# 00_Block_Diagram.net
KiCad netlist of a schematic drawn in Altium Designer
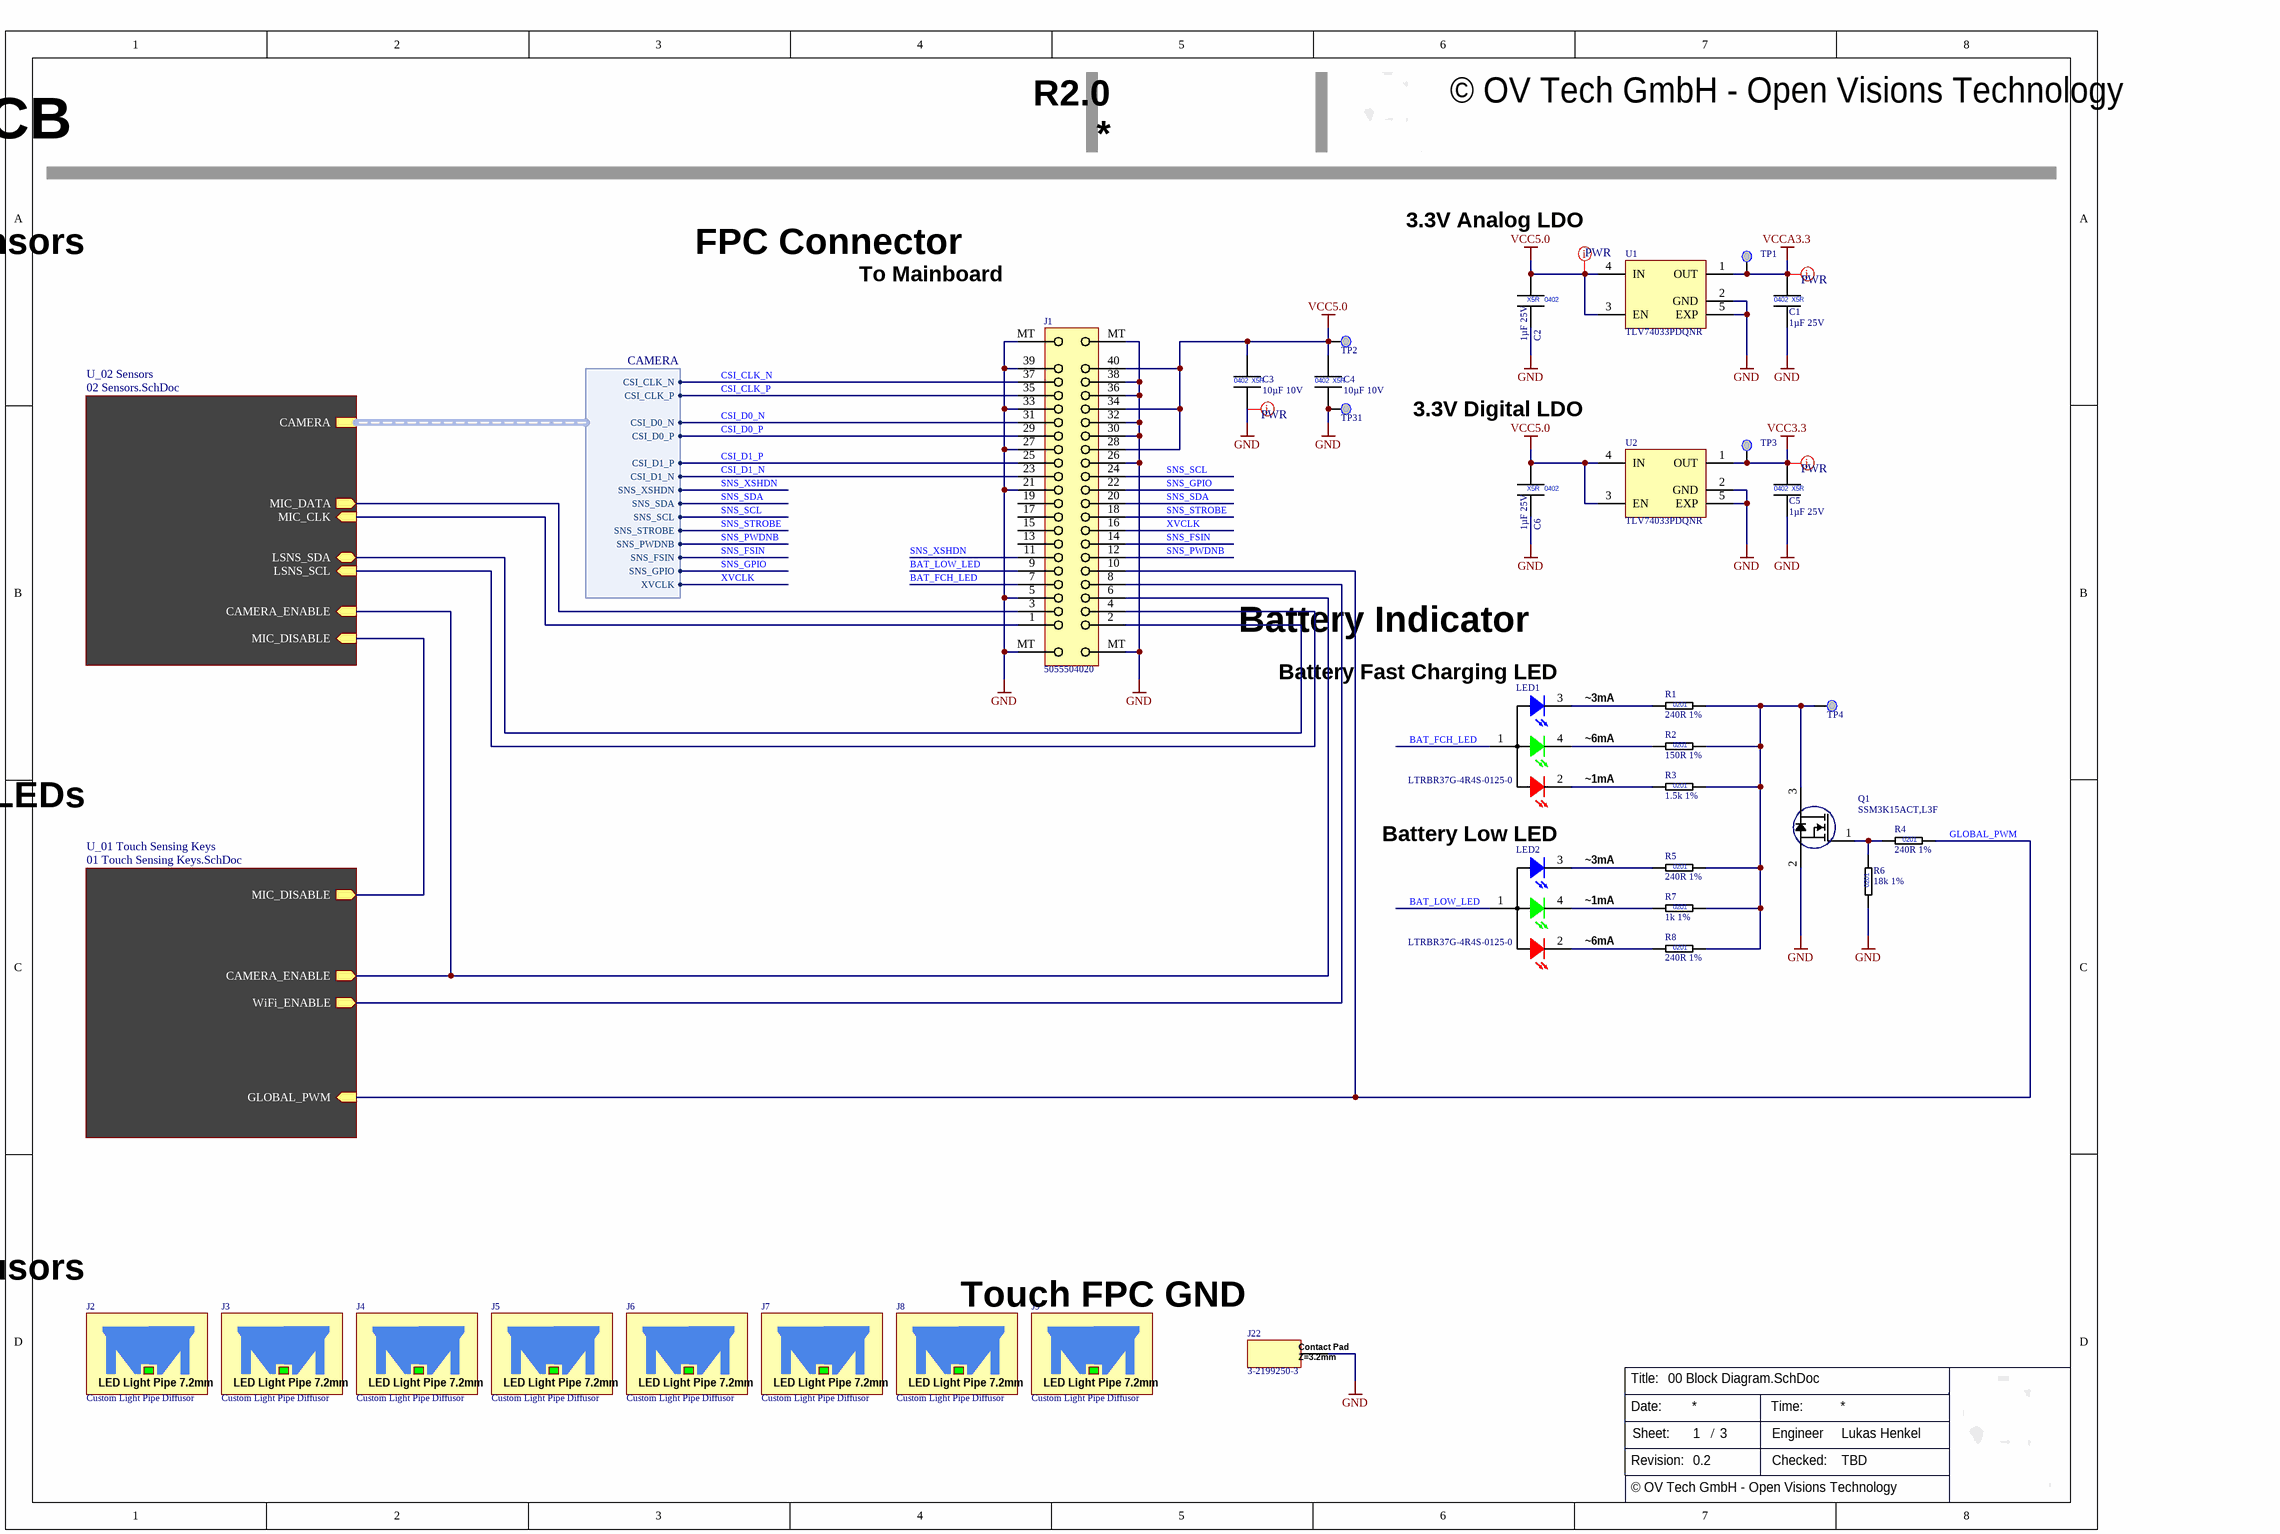
[diagram p0: 00 Block Diagram.SchDoc]

(export (version "E")
  (design (tool "Eeschema 10.0.6"))
  (components
    (comp (ref "C1")
      (value "1µF 25V")
      (footprint "QV_Cap:CAPC1005X06L")
      (description "Multilayer Ceramic Capacitors MLCC - SMD/SMT 0402 25VDC")
      (libsource (lib "QV_Cap") (part "CAP_0402_1µ_25V"))
    )
    (comp (ref "C2")
      (value "1µF 25V")
      (footprint "QV_Cap:CAPC1005X06L")
      (description "Multilayer Ceramic Capacitors MLCC - SMD/SMT 0402 25VDC")
      (libsource (lib "QV_Cap") (part "CAP_0402_1µ_25V"))
    )
    (comp (ref "C3")
      (value "10µF 10V")
      (footprint "QV_Cap:CAPC1005X06L")
      (description "Multilayer Ceramic Capacitors MLCC - SMD/SMT 0402 10VDC")
      (libsource (lib "QV_Cap") (part "CAP_0402_10µ_10V"))
    )
    (comp (ref "C4")
      (value "10µF 10V")
      (footprint "QV_Cap:CAPC1005X06L")
      (description "Multilayer Ceramic Capacitors MLCC - SMD/SMT 0402 10VDC")
      (libsource (lib "QV_Cap") (part "CAP_0402_10µ_10V"))
    )
    (comp (ref "C5")
      (value "1µF 25V")
      (footprint "QV_Cap:CAPC1005X06L")
      (description "Multilayer Ceramic Capacitors MLCC - SMD/SMT 0402 25VDC")
      (libsource (lib "QV_Cap") (part "CAP_0402_1µ_25V"))
    )
    (comp (ref "C6")
      (value "1µF 25V")
      (footprint "QV_Cap:CAPC1005X06L")
      (description "Multilayer Ceramic Capacitors MLCC - SMD/SMT 0402 25VDC")
      (libsource (lib "QV_Cap") (part "CAP_0402_1µ_25V"))
    )
    (comp (ref "J1")
      (value "5055504020")
      (footprint "QV_Con:BOARD-TO-BOARD 40POL_505550-4020")
      (description "Board to Board connector 40Pol Stacking Header 0.4mm Pitch")
      (libsource (lib "QV_Con") (part "Board to Board Connector_5055504020"))
    )
    (comp (ref "J2")
      (value "Custom Light Pipe Diffusor")
      (footprint "QV_ElectroMech:LIGHT_PIPE_DIFFUSOR_CUSTOM")
      (description "Low Profile LED light pipe diffusor")
      (libsource (lib "QV_ElectroMech") (part "LIGHT PIPE_CUSTOM_DIFFUSOR"))
    )
    (comp (ref "J3")
      (value "Custom Light Pipe Diffusor")
      (footprint "QV_ElectroMech:LIGHT_PIPE_DIFFUSOR_CUSTOM")
      (description "Low Profile LED light pipe diffusor")
      (libsource (lib "QV_ElectroMech") (part "LIGHT PIPE_CUSTOM_DIFFUSOR"))
    )
    (comp (ref "J4")
      (value "Custom Light Pipe Diffusor")
      (footprint "QV_ElectroMech:LIGHT_PIPE_DIFFUSOR_CUSTOM")
      (description "Low Profile LED light pipe diffusor")
      (libsource (lib "QV_ElectroMech") (part "LIGHT PIPE_CUSTOM_DIFFUSOR"))
    )
    (comp (ref "J5")
      (value "Custom Light Pipe Diffusor")
      (footprint "QV_ElectroMech:LIGHT_PIPE_DIFFUSOR_CUSTOM")
      (description "Low Profile LED light pipe diffusor")
      (libsource (lib "QV_ElectroMech") (part "LIGHT PIPE_CUSTOM_DIFFUSOR"))
    )
    (comp (ref "J6")
      (value "Custom Light Pipe Diffusor")
      (footprint "QV_ElectroMech:LIGHT_PIPE_DIFFUSOR_CUSTOM")
      (description "Low Profile LED light pipe diffusor")
      (libsource (lib "QV_ElectroMech") (part "LIGHT PIPE_CUSTOM_DIFFUSOR"))
    )
    (comp (ref "J7")
      (value "Custom Light Pipe Diffusor")
      (footprint "QV_ElectroMech:LIGHT_PIPE_DIFFUSOR_CUSTOM")
      (description "Low Profile LED light pipe diffusor")
      (libsource (lib "QV_ElectroMech") (part "LIGHT PIPE_CUSTOM_DIFFUSOR"))
    )
    (comp (ref "J8")
      (value "Custom Light Pipe Diffusor")
      (footprint "QV_ElectroMech:LIGHT_PIPE_DIFFUSOR_CUSTOM")
      (description "Low Profile LED light pipe diffusor")
      (libsource (lib "QV_ElectroMech") (part "LIGHT PIPE_CUSTOM_DIFFUSOR"))
    )
    (comp (ref "J9")
      (value "Custom Light Pipe Diffusor")
      (footprint "QV_ElectroMech:LIGHT_PIPE_DIFFUSOR_CUSTOM")
      (description "Low Profile LED light pipe diffusor")
      (libsource (lib "QV_ElectroMech") (part "LIGHT PIPE_CUSTOM_DIFFUSOR"))
    )
    (comp (ref "J22")
      (value "3-2199250-3")
      (footprint "QV_ElectroMech:Contact Pad_3.2mm_3-2199250-3")
      (description "SMD Contact pad spring loaded 3.2mm")
      (libsource (lib "QV_ElectroMech") (part "PAD_3-2199250-3"))
    )
    (comp (ref "LED1")
      (value "LTRBR37G-4R4S-0125-0")
      (footprint "QV_LED:LED 120X120 LTRB R37G RGB")
      (description "Micro LED Ultra Low Profile 1.2mm X 1.2mm X 0.25mm LTRBR37G")
      (libsource (lib "QV_LED") (part "LED RGB Low Profile_LTRBR37G-4R4S-0125-0"))
    )
    (comp (ref "LED2")
      (value "LTRBR37G-4R4S-0125-0")
      (footprint "QV_LED:LED 120X120 LTRB R37G RGB")
      (description "Micro LED Ultra Low Profile 1.2mm X 1.2mm X 0.25mm LTRBR37G")
      (libsource (lib "QV_LED") (part "LED RGB Low Profile_LTRBR37G-4R4S-0125-0"))
    )
    (comp (ref "Q1")
      (value "SSM3K15ACT,L3F")
      (footprint "QV_Trans:DFN65P100X50-3L")
      (description "MOSFET 30V SGL N-CH TRENCHMOS Logic Level")
      (libsource (lib "QV_Trans") (part "N-Channel MOSFET_SSM3K15ACT,L3F"))
    )
    (comp (ref "R1")
      (value "240R 1%")
      (footprint "QV_Res:RESC0603X03L")
      (description "Thick Film Resistors - SMD 240 OHM 1%")
      (libsource (lib "QV_res") (part "RES_0201_240R_1%"))
    )
    (comp (ref "R2")
      (value "150R 1%")
      (footprint "QV_Res:RESC0603X03L")
      (description "Thick Film Resistors - SMD 150 OHM 1%")
      (libsource (lib "QV_res") (part "RES_0201_150R_1%"))
    )
    (comp (ref "R3")
      (value "1.5k 1%")
      (footprint "QV_Res:RESC0603X03L")
      (description "Thick Film Resistors - SMD 1.5K OHM 1%")
      (libsource (lib "QV_res") (part "RES_0201_1.5k_1%"))
    )
    (comp (ref "R4")
      (value "240R 1%")
      (footprint "QV_Res:RESC0603X03L")
      (description "Thick Film Resistors - SMD 240 OHM 1%")
      (libsource (lib "QV_res") (part "RES_0201_240R_1%"))
    )
    (comp (ref "R5")
      (value "240R 1%")
      (footprint "QV_Res:RESC0603X03L")
      (description "Thick Film Resistors - SMD 240 OHM 1%")
      (libsource (lib "QV_res") (part "RES_0201_240R_1%"))
    )
    (comp (ref "R6")
      (value "18k 1%")
      (footprint "QV_Res:RESC0603X03L")
      (description "Thick Film Resistors - SMD 18K OHM 1%")
      (libsource (lib "QV_res") (part "RES_0201_18k_1%"))
    )
    (comp (ref "R7")
      (value "1k 1%")
      (footprint "QV_Res:RESC0603X03L")
      (description "Thick Film Resistors - SMD 1K OHM 1%")
      (libsource (lib "QV_res") (part "RES_0201_1k_1%"))
    )
    (comp (ref "R8")
      (value "240R 1%")
      (footprint "QV_Res:RESC0603X03L")
      (description "Thick Film Resistors - SMD 240 OHM 1%")
      (libsource (lib "QV_res") (part "RES_0201_240R_1%"))
    )
    (comp (ref "TP1")
      (value "Testpoint 0.5mm")
      (footprint "QV_ElectroMech:TP_0.50mm")
      (libsource (lib "QV_ElectroMech") (part "Testpoint 0.5mm"))
    )
    (comp (ref "TP2")
      (value "Testpoint 0.5mm")
      (footprint "QV_ElectroMech:TP_0.50mm")
      (libsource (lib "QV_ElectroMech") (part "Testpoint 0.5mm"))
    )
    (comp (ref "TP3")
      (value "Testpoint 0.5mm")
      (footprint "QV_ElectroMech:TP_0.50mm")
      (libsource (lib "QV_ElectroMech") (part "Testpoint 0.5mm"))
    )
    (comp (ref "TP4")
      (value "Testpoint 0.5mm")
      (footprint "QV_ElectroMech:TP_0.50mm")
      (libsource (lib "QV_ElectroMech") (part "Testpoint 0.5mm"))
    )
    (comp (ref "TP31")
      (value "Testpoint 0.5mm")
      (footprint "QV_ElectroMech:TP_0.50mm")
      (libsource (lib "QV_ElectroMech") (part "Testpoint 0.5mm"))
    )
    (comp (ref "U1")
      (value "TLV74033PDQNR")
      (footprint "QV_Linear:X2SON-DFN")
      (description "LDO voltage regulator 300mA X2SON")
      (libsource (lib "QV_Linear") (part "LDO 3.3V_TLV74033PDQNR"))
    )
    (comp (ref "U2")
      (value "TLV74033PDQNR")
      (footprint "QV_Linear:X2SON-DFN")
      (description "LDO voltage regulator 300mA X2SON")
      (libsource (lib "QV_Linear") (part "LDO 3.3V_TLV74033PDQNR"))
    )
  )
  (nets
    (net (code "2") (name "/BAT_FCH_LED") (class "Default")
      (node (ref "J1") (pin "7") (pinfunction "7_7") (pintype "passive"))
      (node (ref "LED1") (pin "1") (pinfunction "1_1") (pintype "passive"))
    )
    (net (code "3") (name "/BAT_LOW_LED") (class "Default")
      (node (ref "J1") (pin "9") (pinfunction "9_9") (pintype "passive"))
      (node (ref "LED2") (pin "1") (pinfunction "1_1") (pintype "passive"))
    )
    (net (code "4") (name "/CAMERA_ENABLE") (class "Default")
      (node (ref "J1") (pin "6") (pinfunction "6_6") (pintype "passive"))
    )
    (net (code "5") (name "/CSI_CLK_N") (class "Default")
      (node (ref "J1") (pin "37") (pinfunction "37_37") (pintype "passive"))
    )
    (net (code "6") (name "/CSI_CLK_P") (class "Default")
      (node (ref "J1") (pin "35") (pinfunction "35_35") (pintype "passive"))
    )
    (net (code "7") (name "/CSI_D0_N") (class "Default")
      (node (ref "J1") (pin "31") (pinfunction "31_31") (pintype "passive"))
    )
    (net (code "8") (name "/CSI_D0_P") (class "Default")
      (node (ref "J1") (pin "29") (pinfunction "29_29") (pintype "passive"))
    )
    (net (code "9") (name "/CSI_D1_N") (class "Default")
      (node (ref "J1") (pin "23") (pinfunction "23_23") (pintype "passive"))
    )
    (net (code "10") (name "/CSI_D1_P") (class "Default")
      (node (ref "J1") (pin "25") (pinfunction "25_25") (pintype "passive"))
    )
    (net (code "11") (name "/GLOBAL_PWM") (class "Default")
      (node (ref "J1") (pin "10") (pinfunction "10_10") (pintype "passive"))
      (node (ref "R4") (pin "2") (pinfunction "2_2") (pintype "passive"))
    )
    (net (code "12") (name "/LSNS_SCL") (class "Default")
      (node (ref "J1") (pin "4") (pinfunction "4_4") (pintype "passive"))
    )
    (net (code "13") (name "/LSNS_SDA") (class "Default")
      (node (ref "J1") (pin "2") (pinfunction "2_2") (pintype "passive"))
    )
    (net (code "14") (name "/MIC_CLK") (class "Default")
      (node (ref "J1") (pin "1") (pinfunction "1_1") (pintype "passive"))
    )
    (net (code "15") (name "/MIC_DATA") (class "Default")
      (node (ref "J1") (pin "3") (pinfunction "3_3") (pintype "passive"))
    )
    (net (code "17") (name "/SNS_FSIN") (class "Default")
      (node (ref "J1") (pin "14") (pinfunction "14_14") (pintype "passive"))
    )
    (net (code "18") (name "/SNS_GPIO") (class "Default")
      (node (ref "J1") (pin "22") (pinfunction "22_22") (pintype "passive"))
    )
    (net (code "19") (name "/SNS_PWDNB") (class "Default")
      (node (ref "J1") (pin "12") (pinfunction "12_12") (pintype "passive"))
    )
    (net (code "20") (name "/SNS_SCL") (class "Default")
      (node (ref "J1") (pin "24") (pinfunction "24_24") (pintype "passive"))
    )
    (net (code "21") (name "/SNS_SDA") (class "Default")
      (node (ref "J1") (pin "20") (pinfunction "20_20") (pintype "passive"))
    )
    (net (code "22") (name "/SNS_STROBE") (class "Default")
      (node (ref "J1") (pin "18") (pinfunction "18_18") (pintype "passive"))
    )
    (net (code "23") (name "/SNS_XSHDN") (class "Default")
      (node (ref "J1") (pin "11") (pinfunction "11_11") (pintype "passive"))
    )
    (net (code "24") (name "/WiFi_ENABLE") (class "Default")
      (node (ref "J1") (pin "8") (pinfunction "8_8") (pintype "passive"))
    )
    (net (code "25") (name "/XVCLK") (class "Default")
      (node (ref "J1") (pin "16") (pinfunction "16_16") (pintype "passive"))
    )
    (net (code "27") (name "GND") (class "Default")
      (node (ref "C1") (pin "2") (pinfunction "2_2") (pintype "passive"))
      (node (ref "C2") (pin "2") (pinfunction "2_2") (pintype "passive"))
      (node (ref "C3") (pin "2") (pinfunction "2_2") (pintype "passive"))
      (node (ref "C4") (pin "2") (pinfunction "2_2") (pintype "passive"))
      (node (ref "C5") (pin "2") (pinfunction "2_2") (pintype "passive"))
      (node (ref "C6") (pin "2") (pinfunction "2_2") (pintype "passive"))
      (node (ref "J1") (pin "21") (pinfunction "21_21") (pintype "passive"))
      (node (ref "J1") (pin "26") (pinfunction "26_26") (pintype "passive"))
      (node (ref "J1") (pin "27") (pinfunction "27_27") (pintype "passive"))
      (node (ref "J1") (pin "30") (pinfunction "30_30") (pintype "passive"))
      (node (ref "J1") (pin "32") (pinfunction "32_32") (pintype "passive"))
      (node (ref "J1") (pin "33") (pinfunction "33_33") (pintype "passive"))
      (node (ref "J1") (pin "36") (pinfunction "36_36") (pintype "passive"))
      (node (ref "J1") (pin "38") (pinfunction "38_38") (pintype "passive"))
      (node (ref "J1") (pin "39") (pinfunction "39_39") (pintype "passive"))
      (node (ref "J1") (pin "5") (pinfunction "5_5") (pintype "passive"))
      (node (ref "J1") (pin "MT") (pinfunction "MT_MT") (pintype "passive"))
      (node (ref "J22") (pin "1") (pinfunction "1_1") (pintype "passive"))
      (node (ref "Q1") (pin "2") (pinfunction "S_2") (pintype "passive"))
      (node (ref "R6") (pin "1") (pinfunction "1_1") (pintype "passive"))
      (node (ref "TP31") (pin "TP") (pinfunction "TP_TP") (pintype "passive"))
      (node (ref "U1") (pin "2") (pinfunction "GND_2") (pintype "passive"))
      (node (ref "U1") (pin "5") (pinfunction "EXP_5") (pintype "passive"))
      (node (ref "U2") (pin "2") (pinfunction "GND_2") (pintype "passive"))
      (node (ref "U2") (pin "5") (pinfunction "EXP_5") (pintype "passive"))
    )
    (net (code "28") (name "Net-(LED1-Pad2)") (class "Default")
      (node (ref "LED1") (pin "2") (pinfunction "2_2") (pintype "passive"))
      (node (ref "R3") (pin "1") (pinfunction "1_1") (pintype "passive"))
    )
    (net (code "29") (name "Net-(LED1-Pad3)") (class "Default")
      (node (ref "LED1") (pin "3") (pinfunction "3_3") (pintype "passive"))
      (node (ref "R1") (pin "1") (pinfunction "1_1") (pintype "passive"))
    )
    (net (code "30") (name "Net-(LED1-Pad4)") (class "Default")
      (node (ref "LED1") (pin "4") (pinfunction "4_4") (pintype "passive"))
      (node (ref "R2") (pin "1") (pinfunction "1_1") (pintype "passive"))
    )
    (net (code "31") (name "Net-(LED2-Pad2)") (class "Default")
      (node (ref "LED2") (pin "2") (pinfunction "2_2") (pintype "passive"))
      (node (ref "R8") (pin "1") (pinfunction "1_1") (pintype "passive"))
    )
    (net (code "32") (name "Net-(LED2-Pad3)") (class "Default")
      (node (ref "LED2") (pin "3") (pinfunction "3_3") (pintype "passive"))
      (node (ref "R5") (pin "1") (pinfunction "1_1") (pintype "passive"))
    )
    (net (code "33") (name "Net-(LED2-Pad4)") (class "Default")
      (node (ref "LED2") (pin "4") (pinfunction "4_4") (pintype "passive"))
      (node (ref "R7") (pin "1") (pinfunction "1_1") (pintype "passive"))
    )
    (net (code "34") (name "Net-(Q1-D)") (class "Default")
      (node (ref "Q1") (pin "3") (pinfunction "D_3") (pintype "passive"))
      (node (ref "R1") (pin "2") (pinfunction "2_2") (pintype "passive"))
      (node (ref "R2") (pin "2") (pinfunction "2_2") (pintype "passive"))
      (node (ref "R3") (pin "2") (pinfunction "2_2") (pintype "passive"))
      (node (ref "R5") (pin "2") (pinfunction "2_2") (pintype "passive"))
      (node (ref "R7") (pin "2") (pinfunction "2_2") (pintype "passive"))
      (node (ref "R8") (pin "2") (pinfunction "2_2") (pintype "passive"))
      (node (ref "TP4") (pin "TP") (pinfunction "TP_TP") (pintype "passive"))
    )
    (net (code "35") (name "Net-(Q1-G)") (class "Default")
      (node (ref "Q1") (pin "1") (pinfunction "G_1") (pintype "passive"))
      (node (ref "R4") (pin "1") (pinfunction "1_1") (pintype "passive"))
      (node (ref "R6") (pin "2") (pinfunction "2_2") (pintype "passive"))
    )
    (net (code "36") (name "VCC3.3") (class "Default")
      (node (ref "C5") (pin "1") (pinfunction "1_1") (pintype "passive"))
      (node (ref "TP3") (pin "TP") (pinfunction "TP_TP") (pintype "passive"))
      (node (ref "U2") (pin "1") (pinfunction "OUT_1") (pintype "passive"))
    )
    (net (code "37") (name "VCC5.0") (class "Default")
      (node (ref "C2") (pin "1") (pinfunction "1_1") (pintype "passive"))
      (node (ref "C3") (pin "1") (pinfunction "1_1") (pintype "passive"))
      (node (ref "C4") (pin "1") (pinfunction "1_1") (pintype "passive"))
      (node (ref "C6") (pin "1") (pinfunction "1_1") (pintype "passive"))
      (node (ref "J1") (pin "28") (pinfunction "28_28") (pintype "passive"))
      (node (ref "J1") (pin "34") (pinfunction "34_34") (pintype "passive"))
      (node (ref "J1") (pin "40") (pinfunction "40_40") (pintype "passive"))
      (node (ref "TP2") (pin "TP") (pinfunction "TP_TP") (pintype "passive"))
      (node (ref "U1") (pin "3") (pinfunction "EN_3") (pintype "passive"))
      (node (ref "U1") (pin "4") (pinfunction "IN_4") (pintype "passive"))
      (node (ref "U2") (pin "3") (pinfunction "EN_3") (pintype "passive"))
      (node (ref "U2") (pin "4") (pinfunction "IN_4") (pintype "passive"))
    )
    (net (code "38") (name "VCCA3.3") (class "Default")
      (node (ref "C1") (pin "1") (pinfunction "1_1") (pintype "passive"))
      (node (ref "TP1") (pin "TP") (pinfunction "TP_TP") (pintype "passive"))
      (node (ref "U1") (pin "1") (pinfunction "OUT_1") (pintype "passive"))
    )
    (net (code "39") (name "unconnected-(J1-Pad13)") (class "Default")
      (node (ref "J1") (pin "13") (pinfunction "13_13") (pintype "passive"))
    )
    (net (code "40") (name "unconnected-(J1-Pad15)") (class "Default")
      (node (ref "J1") (pin "15") (pinfunction "15_15") (pintype "passive"))
    )
    (net (code "41") (name "unconnected-(J1-Pad17)") (class "Default")
      (node (ref "J1") (pin "17") (pinfunction "17_17") (pintype "passive"))
    )
    (net (code "42") (name "unconnected-(J1-Pad19)") (class "Default")
      (node (ref "J1") (pin "19") (pinfunction "19_19") (pintype "passive"))
    )
  )
)
